# F73-M-V1_0.net
KiCad netlist of a schematic drawn in Altium Designer
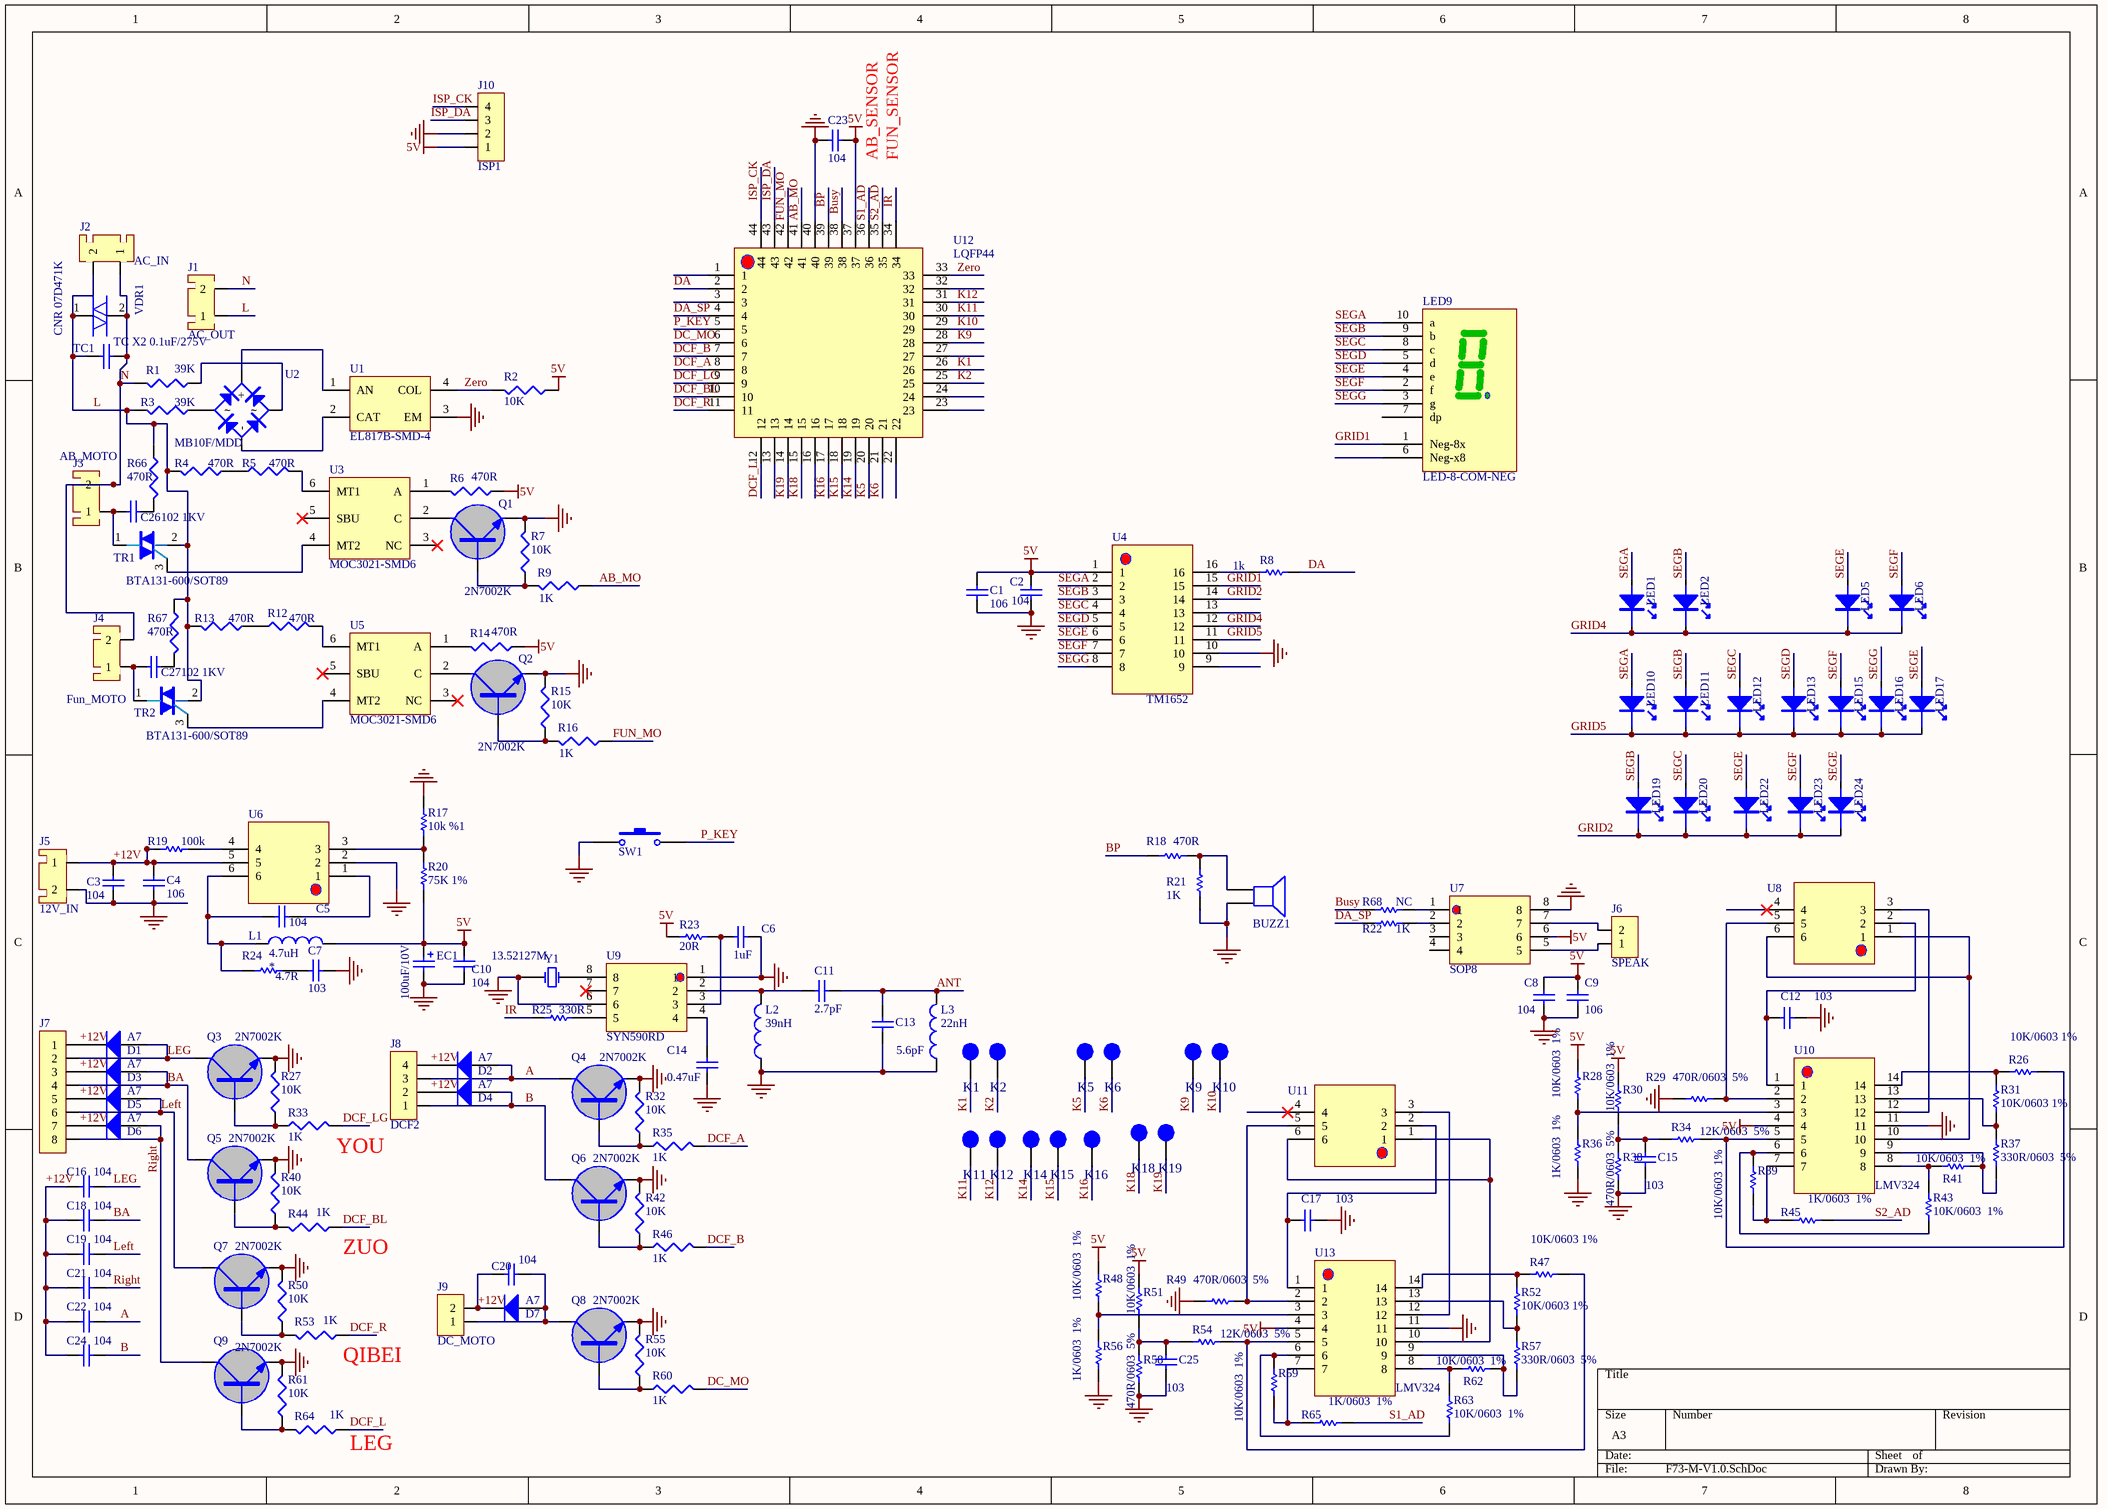
[diagram p0: F73-M-V1.0.SchDoc]

(export (version "E")
  (design (tool "Eeschema 10.0.6"))
  (components
    (comp (ref "BUZZ1")
      (value "Speaker")
      (footprint "BUZ-1407-7.5")
      (description "Loudspeaker")
      (fields (field (name "MANUFACTURER") "Generic Components"))
      (libsource (lib "Miscellaneous Devices") (part "Speaker"))
    )
    (comp (ref "C1")
      (value "106")
      (footprint "0805C")
      (description "Capacitor")
      (fields
        (field (name "MANUFACTURER") "Generic Components")
        (field (name "PUBLISHER") "Altium Hobart Technology Centre")
      )
      (libsource (lib "Miscellaneous Devices") (part "Cap"))
    )
    (comp (ref "C2")
      (value "104")
      (footprint "0603C")
      (description "Capacitor")
      (fields
        (field (name "MANUFACTURER") "Generic Components")
        (field (name "PUBLISHER") "Altium Hobart Technology Centre")
      )
      (libsource (lib "Miscellaneous Devices") (part "Cap"))
    )
    (comp (ref "C3")
      (value "104")
      (footprint "0603C")
      (description "Capacitor")
      (fields (field (name "PUBLISHER") "Altium Limited"))
      (libsource (lib "Phil") (part "Cap"))
    )
    (comp (ref "C4")
      (value "106")
      (footprint "0805C")
      (description "Capacitor")
      (fields
        (field (name "MANUFACTURER") "Generic Components")
        (field (name "PUBLISHER") "Altium Hobart Technology Centre")
      )
      (libsource (lib "Miscellaneous Devices") (part "Cap"))
    )
    (comp (ref "C5")
      (value "104")
      (footprint "0603C")
      (description "Capacitor")
      (fields
        (field (name "MANUFACTURER") "Generic Components")
        (field (name "PUBLISHER") "Altium Hobart Technology Centre")
      )
      (libsource (lib "Miscellaneous Devices") (part "Cap"))
    )
    (comp (ref "C6")
      (value "1uF")
      (footprint "0603C")
      (description "Capacitor")
      (fields (field (name "PUBLISHER") "Altium Limited"))
      (libsource (lib "Phil") (part "Cap"))
    )
    (comp (ref "C7")
      (value "103")
      (footprint "0603C")
      (description "Capacitor")
      (fields (field (name "PUBLISHER") "Altium Limited"))
      (libsource (lib "Phil") (part "Cap"))
    )
    (comp (ref "C8")
      (value "104")
      (footprint "0603C")
      (description "Capacitor")
      (fields
        (field (name "MANUFACTURER") "Generic Components")
        (field (name "PUBLISHER") "Altium Hobart Technology Centre")
      )
      (libsource (lib "Miscellaneous Devices") (part "Cap"))
    )
    (comp (ref "C9")
      (value "106")
      (footprint "0805C")
      (description "Capacitor")
      (fields
        (field (name "MANUFACTURER") "Generic Components")
        (field (name "PUBLISHER") "Altium Hobart Technology Centre")
      )
      (libsource (lib "Miscellaneous Devices") (part "Cap"))
    )
    (comp (ref "C10")
      (value "104")
      (footprint "0603C")
      (description "Capacitor")
      (fields
        (field (name "MANUFACTURER") "Generic Components")
        (field (name "PUBLISHER") "Altium Hobart Technology Centre")
      )
      (libsource (lib "Miscellaneous Devices") (part "Cap"))
    )
    (comp (ref "C11")
      (value "2.7pF")
      (footprint "0603C")
      (description "Capacitor")
      (fields (field (name "PUBLISHER") "Altium Limited"))
      (libsource (lib "Phil") (part "Cap"))
    )
    (comp (ref "C12")
      (value "103")
      (footprint "0603C")
      (description "Capacitor")
      (fields (field (name "PUBLISHER") "Altium Limited"))
      (libsource (lib "Phil") (part "Cap"))
    )
    (comp (ref "C13")
      (value "5.6pF")
      (footprint "0603C")
      (description "Capacitor")
      (fields (field (name "PUBLISHER") "Altium Limited"))
      (libsource (lib "Phil") (part "Cap"))
    )
    (comp (ref "C14")
      (value "0.47uF")
      (footprint "0603C")
      (description "Capacitor")
      (fields (field (name "PUBLISHER") "Altium Limited"))
      (libsource (lib "Phil") (part "Cap"))
    )
    (comp (ref "C15")
      (value "103")
      (footprint "0603C")
      (description "Capacitor")
      (fields (field (name "PUBLISHER") "Altium Limited"))
      (libsource (lib "Phil") (part "Cap"))
    )
    (comp (ref "C16")
      (value "104")
      (footprint "0603C")
      (description "Capacitor")
      (fields (field (name "PUBLISHER") "Altium Limited"))
      (libsource (lib "Phil") (part "Cap"))
    )
    (comp (ref "C17")
      (value "103")
      (footprint "0603C")
      (description "Capacitor")
      (fields (field (name "PUBLISHER") "Altium Limited"))
      (libsource (lib "Phil") (part "Cap"))
    )
    (comp (ref "C18")
      (value "104")
      (footprint "0603C")
      (description "Capacitor")
      (fields (field (name "PUBLISHER") "Altium Limited"))
      (libsource (lib "Phil") (part "Cap"))
    )
    (comp (ref "C19")
      (value "104")
      (footprint "0603C")
      (description "Capacitor")
      (fields (field (name "PUBLISHER") "Altium Limited"))
      (libsource (lib "Phil") (part "Cap"))
    )
    (comp (ref "C20")
      (value "104")
      (footprint "0603C")
      (description "Capacitor")
      (fields
        (field (name "MANUFACTURER") "Generic Components")
        (field (name "PUBLISHER") "Altium Hobart Technology Centre")
      )
      (libsource (lib "Miscellaneous Devices") (part "Cap"))
    )
    (comp (ref "C21")
      (value "104")
      (footprint "0603C")
      (description "Capacitor")
      (fields (field (name "PUBLISHER") "Altium Limited"))
      (libsource (lib "Phil") (part "Cap"))
    )
    (comp (ref "C22")
      (value "104")
      (footprint "0603C")
      (description "Capacitor")
      (fields (field (name "PUBLISHER") "Altium Limited"))
      (libsource (lib "Phil") (part "Cap"))
    )
    (comp (ref "C23")
      (value "104")
      (footprint "0603C")
      (description "Capacitor")
      (fields (field (name "PUBLISHER") "Altium Limited"))
      (libsource (lib "HF-FOUR-M-1.0") (part "Cap"))
    )
    (comp (ref "C24")
      (value "104")
      (footprint "0603C")
      (description "Capacitor")
      (fields (field (name "PUBLISHER") "Altium Limited"))
      (libsource (lib "Phil") (part "Cap"))
    )
    (comp (ref "C25")
      (value "103")
      (footprint "0603C")
      (description "Capacitor")
      (fields (field (name "PUBLISHER") "Altium Limited"))
      (libsource (lib "Phil") (part "Cap"))
    )
    (comp (ref "C26")
      (value "102 1KV")
      (footprint "1206C")
      (description "Capacitor")
      (fields
        (field (name "MANUFACTURER") "Generic Components")
        (field (name "PUBLISHER") "Altium Hobart Technology Centre")
      )
      (libsource (lib "Miscellaneous Devices") (part "Cap"))
    )
    (comp (ref "C27")
      (value "102 1KV")
      (footprint "1206C")
      (description "Capacitor")
      (fields
        (field (name "MANUFACTURER") "Generic Components")
        (field (name "PUBLISHER") "Altium Hobart Technology Centre")
      )
      (libsource (lib "Miscellaneous Devices") (part "Cap"))
    )
    (comp (ref "D1")
      (value "A7")
      (footprint "SOD-123FL_L2.8-W1.8-LS3.7")
      (description "1 Amp General Purpose Rectifier")
      (fields (field (name "PUBLISHER") "Altium Limited"))
      (libsource (lib "Phil") (part "Diode 1N4007"))
    )
    (comp (ref "D2")
      (value "A7")
      (footprint "SOD-123FL_L2.8-W1.8-LS3.7")
      (description "1 Amp General Purpose Rectifier")
      (fields (field (name "PUBLISHER") "Altium Limited"))
      (libsource (lib "Phil") (part "Diode 1N4007"))
    )
    (comp (ref "D3")
      (value "A7")
      (footprint "SOD-123FL_L2.8-W1.8-LS3.7")
      (description "1 Amp General Purpose Rectifier")
      (fields (field (name "PUBLISHER") "Altium Limited"))
      (libsource (lib "Phil") (part "Diode 1N4007"))
    )
    (comp (ref "D4")
      (value "A7")
      (footprint "SOD-123FL_L2.8-W1.8-LS3.7")
      (description "1 Amp General Purpose Rectifier")
      (fields (field (name "PUBLISHER") "Altium Limited"))
      (libsource (lib "Phil") (part "Diode 1N4007"))
    )
    (comp (ref "D5")
      (value "A7")
      (footprint "SOD-123FL_L2.8-W1.8-LS3.7")
      (description "1 Amp General Purpose Rectifier")
      (fields (field (name "PUBLISHER") "Altium Limited"))
      (libsource (lib "Phil") (part "Diode 1N4007"))
    )
    (comp (ref "D6")
      (value "A7")
      (footprint "SOD-123FL_L2.8-W1.8-LS3.7")
      (description "1 Amp General Purpose Rectifier")
      (fields (field (name "PUBLISHER") "Altium Limited"))
      (libsource (lib "Phil") (part "Diode 1N4007"))
    )
    (comp (ref "D7")
      (value "A7")
      (footprint "SOD-123FL_L2.8-W1.8-LS3.7")
      (description "1 Amp General Purpose Rectifier")
      (fields (field (name "PUBLISHER") "Altium Limited"))
      (libsource (lib "Phil") (part "Diode 1N4007"))
    )
    (comp (ref "EC1")
      (value "100uF/10V")
      (footprint "CAP SMD 6.3*5.5mm")
      (description "Polarized Capacitor (Radial)")
      (fields
        (field (name "MANUFACTURER") "Generic Components")
        (field (name "PUBLISHER") "Altium Hobart Technology Centre")
      )
      (libsource (lib "Miscellaneous Devices") (part "Cap Pol1"))
    )
    (comp (ref "J1")
      (value "AC_OUT")
      (footprint "K-VH3.96-3P")
      (libsource (lib "SCH Connector(2019-4-13)") (part "PITCH3.96-5.0-2A"))
    )
    (comp (ref "J2")
      (value "AC_IN")
      (footprint "K-VH3.96-3P")
      (libsource (lib "") (part "PITCH3.96-5.0-2A_1"))
    )
    (comp (ref "J3")
      (value "AB_MOTO")
      (footprint "K-VH3.96-3P")
      (libsource (lib "SCH Connector(2019-4-13)") (part "PITCH3.96-5.0-2A"))
    )
    (comp (ref "J4")
      (value "Fun_MOTO")
      (footprint "K-VH3.96-3P")
      (libsource (lib "SCH Connector(2019-4-13)") (part "PITCH3.96-5.0-2A"))
    )
    (comp (ref "J5")
      (value "12V_IN")
      (footprint "CON2-SMD-XHB 2*2.5MM")
      (libsource (lib "SCH Connector(2019-4-13)") (part "PITCH2.5-2A"))
    )
    (comp (ref "J6") (value "SPEAK") (footprint "CON2-SMD_PH2.0-1X2PW") (libsource (lib "") (part "CON2_1")))
    (comp (ref "J7")
      (value "~")
      (footprint "CON8-SMD-XHB 8*2.5MM")
      (libsource (lib "HF-FOUR-M-1.0") (part "CON8"))
    )
    (comp (ref "J8")
      (value "DCF2")
      (footprint "CON4-SMD_4P-P2.54_XH2.54-4AB")
      (libsource (lib "Phil") (part "CON4"))
    )
    (comp (ref "J9")
      (value "DC_MOTO")
      (footprint "CON2-SMD-XHB 2*2.5MM")
      (libsource (lib "Phil") (part "CON2"))
    )
    (comp (ref "J10") (value "ISP1") (footprint "CON4 -2.54-H") (libsource (lib "") (part "CON4_1")))
    (comp (ref "K1")
      (value "Φ15 H8mm弹簧")
      (footprint "TK_HF-13*13*8")
      (libsource (lib "HF-FOUR-M-1.0") (part "TOUCH-PAD"))
    )
    (comp (ref "K2")
      (value "Φ15 H8mm弹簧")
      (footprint "TK_HF-13*13*8")
      (libsource (lib "HF-FOUR-M-1.0") (part "TOUCH-PAD"))
    )
    (comp (ref "K5")
      (value "Φ15 H8mm弹簧")
      (footprint "TK_HF-13*13*8")
      (libsource (lib "HF-FOUR-M-1.0") (part "TOUCH-PAD"))
    )
    (comp (ref "K6")
      (value "Φ15 H8mm弹簧")
      (footprint "TK_HF-13*13*8")
      (libsource (lib "HF-FOUR-M-1.0") (part "TOUCH-PAD"))
    )
    (comp (ref "K9")
      (value "Φ15 H8mm弹簧")
      (footprint "TK_HF-13*13*8")
      (libsource (lib "HF-FOUR-M-1.0") (part "TOUCH-PAD"))
    )
    (comp (ref "K10")
      (value "Φ15 H8mm弹簧")
      (footprint "TK_HF-13*13*8")
      (libsource (lib "HF-FOUR-M-1.0") (part "TOUCH-PAD"))
    )
    (comp (ref "K11")
      (value "Φ15 H8mm弹簧")
      (footprint "TK_HF-13*13*8")
      (libsource (lib "HF-FOUR-M-1.0") (part "TOUCH-PAD"))
    )
    (comp (ref "K12")
      (value "Φ15 H8mm弹簧")
      (footprint "TK_HF-13*13*8")
      (libsource (lib "HF-FOUR-M-1.0") (part "TOUCH-PAD"))
    )
    (comp (ref "K14")
      (value "Φ15 H8mm弹簧")
      (footprint "TK_HF-13*13*8")
      (libsource (lib "HF-FOUR-M-1.0") (part "TOUCH-PAD"))
    )
    (comp (ref "K15")
      (value "Φ15 H8mm弹簧")
      (footprint "TK_HF-13*13*8")
      (libsource (lib "HF-FOUR-M-1.0") (part "TOUCH-PAD"))
    )
    (comp (ref "K16")
      (value "Φ15 H8mm弹簧")
      (footprint "TK_HF-13*13*8")
      (libsource (lib "HF-FOUR-M-1.0") (part "TOUCH-PAD"))
    )
    (comp (ref "K18")
      (value "Φ15 H8mm弹簧")
      (footprint "TK_HF-13*13*8")
      (libsource (lib "HF-FOUR-M-1.0") (part "TOUCH-PAD"))
    )
    (comp (ref "K19")
      (value "Φ15 H8mm弹簧")
      (footprint "TK_HF-13*13*8")
      (libsource (lib "HF-FOUR-M-1.0") (part "TOUCH-PAD"))
    )
    (comp (ref "L1")
      (value "4.7uH")
      (footprint "INDC5050")
      (description "Inductor")
      (fields (field (name "ALTIUM_VALUE") "*") (field (name "PUBLISHER") "Altium Limited"))
      (libsource (lib "Phil") (part "Inductor"))
    )
    (comp (ref "L2")
      (value "39nH")
      (footprint "0603R")
      (description "Inductor")
      (fields (field (name "PUBLISHER") "Altium Limited"))
      (libsource (lib "Phil") (part "Inductor"))
    )
    (comp (ref "L3")
      (value "22nH")
      (footprint "0603R")
      (description "Inductor")
      (fields (field (name "PUBLISHER") "Altium Limited"))
      (libsource (lib "Phil") (part "Inductor"))
    )
    (comp (ref "LED1") (value "LED_0603") (footprint "LED_0603") (libsource (lib "Phil") (part "LED")))
    (comp (ref "LED2") (value "LED_0603") (footprint "LED_0603") (libsource (lib "Phil") (part "LED")))
    (comp (ref "LED5") (value "LED_0603") (footprint "LED_0603") (libsource (lib "Phil") (part "LED")))
    (comp (ref "LED6") (value "LED_0603") (footprint "LED_0603") (libsource (lib "Phil") (part "LED")))
    (comp (ref "LED9")
      (value "LED-8-COM-NEG")
      (footprint "LED1B-10P(7.5*14*H8.5 P2.54*10.16)")
      (libsource (lib "F73-M-V1.0") (part "LED-8-COM-NEG"))
    )
    (comp (ref "LED10") (value "LED_0603") (footprint "LED_0603") (libsource (lib "Phil") (part "LED")))
    (comp (ref "LED11") (value "LED_0603") (footprint "LED_0603") (libsource (lib "Phil") (part "LED")))
    (comp (ref "LED12") (value "LED_0603") (footprint "LED_0603") (libsource (lib "Phil") (part "LED")))
    (comp (ref "LED13") (value "LED_0603") (footprint "LED_0603") (libsource (lib "Phil") (part "LED")))
    (comp (ref "LED15") (value "LED_0603") (footprint "LED_0603") (libsource (lib "Phil") (part "LED")))
    (comp (ref "LED16") (value "LED_0603") (footprint "LED_0603") (libsource (lib "Phil") (part "LED")))
    (comp (ref "LED17") (value "LED_0603") (footprint "LED_0603") (libsource (lib "Phil") (part "LED")))
    (comp (ref "LED19") (value "LED_0603") (footprint "LED_0603") (libsource (lib "Phil") (part "LED")))
    (comp (ref "LED20") (value "LED_0603") (footprint "LED_0603") (libsource (lib "Phil") (part "LED")))
    (comp (ref "LED22") (value "LED_0603") (footprint "LED_0603") (libsource (lib "Phil") (part "LED")))
    (comp (ref "LED23") (value "LED_0603") (footprint "LED_0603") (libsource (lib "Phil") (part "LED")))
    (comp (ref "LED24") (value "LED_0603") (footprint "LED_0603") (libsource (lib "Phil") (part "LED")))
    (comp (ref "Q1")
      (value "2N7002K")
      (footprint "SOT-23 - MOS")
      (libsource (lib "SCH-Transistor-Triac-Mosfet(2018-9-19-1)") (part "NPN-8050-BCE-25V/500mA"))
    )
    (comp (ref "Q2")
      (value "2N7002K")
      (footprint "SOT-23 - MOS")
      (libsource (lib "SCH-Transistor-Triac-Mosfet(2018-9-19-1)") (part "NPN-8050-BCE-25V/500mA"))
    )
    (comp (ref "Q3")
      (value "2N7002K")
      (footprint "SOT-23 - MOS")
      (libsource (lib "SCH-Transistor-Triac-Mosfet(2018-9-19-1)") (part "NPN-8050-BCE-25V/500mA"))
    )
    (comp (ref "Q4")
      (value "2N7002K")
      (footprint "SOT-23 - MOS")
      (libsource (lib "SCH-Transistor-Triac-Mosfet(2018-9-19-1)") (part "NPN-8050-BCE-25V/500mA"))
    )
    (comp (ref "Q5")
      (value "2N7002K")
      (footprint "SOT-23 - MOS")
      (libsource (lib "SCH-Transistor-Triac-Mosfet(2018-9-19-1)") (part "NPN-8050-BCE-25V/500mA"))
    )
    (comp (ref "Q6")
      (value "2N7002K")
      (footprint "SOT-23 - MOS")
      (libsource (lib "SCH-Transistor-Triac-Mosfet(2018-9-19-1)") (part "NPN-8050-BCE-25V/500mA"))
    )
    (comp (ref "Q7")
      (value "2N7002K")
      (footprint "SOT-23 - MOS")
      (libsource (lib "SCH-Transistor-Triac-Mosfet(2018-9-19-1)") (part "NPN-8050-BCE-25V/500mA"))
    )
    (comp (ref "Q8")
      (value "2N7002K")
      (footprint "SOT-23 - MOS")
      (libsource (lib "SCH-Transistor-Triac-Mosfet(2018-9-19-1)") (part "NPN-8050-BCE-25V/500mA"))
    )
    (comp (ref "Q9")
      (value "2N7002K")
      (footprint "SOT-23 - MOS")
      (libsource (lib "SCH-Transistor-Triac-Mosfet(2018-9-19-1)") (part "NPN-8050-BCE-25V/500mA"))
    )
    (comp (ref "R1")
      (value "39K")
      (footprint "1206R")
      (libsource (lib "SCH Resistor(2019-6-10)") (part "1Ω±1%/0805-1206"))
    )
    (comp (ref "R2")
      (value "10K")
      (footprint "0603")
      (libsource (lib "SCH Resistor(2019-6-10)") (part "1Ω±1%/0603-0805"))
    )
    (comp (ref "R3")
      (value "39K")
      (footprint "1206R")
      (libsource (lib "SCH Resistor(2019-6-10)") (part "1Ω±1%/0805-1206"))
    )
    (comp (ref "R4")
      (value "470R")
      (footprint "1206R")
      (libsource (lib "SCH Resistor(2019-6-10)") (part "1Ω±1%/0805-1206"))
    )
    (comp (ref "R5")
      (value "470R")
      (footprint "1206R")
      (libsource (lib "SCH Resistor(2019-6-10)") (part "1Ω±1%/0805-1206"))
    )
    (comp (ref "R6")
      (value "470R")
      (footprint "0603")
      (libsource (lib "SCH Resistor(2019-6-10)") (part "1Ω±1%/0603-0805"))
    )
    (comp (ref "R7")
      (value "10K")
      (footprint "0603")
      (libsource (lib "SCH Resistor(2019-6-10)") (part "1Ω±1%/0603-0805"))
    )
    (comp (ref "R8")
      (value "1k")
      (footprint "0603R")
      (description "Resistor")
      (fields (field (name "PUBLISHER") "Altium Limited"))
      (libsource (lib "Phil") (part "Res1"))
    )
    (comp (ref "R9")
      (value "1K")
      (footprint "0603")
      (libsource (lib "SCH Resistor(2019-6-10)") (part "1Ω±1%/0603-0805"))
    )
    (comp (ref "R12")
      (value "470R")
      (footprint "1206R")
      (libsource (lib "SCH Resistor(2019-6-10)") (part "1Ω±1%/0805-1206"))
    )
    (comp (ref "R13")
      (value "470R")
      (footprint "1206R")
      (libsource (lib "SCH Resistor(2019-6-10)") (part "1Ω±1%/0805-1206"))
    )
    (comp (ref "R14")
      (value "470R")
      (footprint "0603")
      (libsource (lib "SCH Resistor(2019-6-10)") (part "1Ω±1%/0603-0805"))
    )
    (comp (ref "R15")
      (value "10K")
      (footprint "0603")
      (libsource (lib "SCH Resistor(2019-6-10)") (part "1Ω±1%/0603-0805"))
    )
    (comp (ref "R16")
      (value "1K")
      (footprint "0603")
      (libsource (lib "SCH Resistor(2019-6-10)") (part "1Ω±1%/0603-0805"))
    )
    (comp (ref "R17")
      (value "10k %1")
      (footprint "0603R")
      (description "Resistor")
      (fields (field (name "PUBLISHER") "Altium Limited"))
      (libsource (lib "Phil") (part "Res1"))
    )
    (comp (ref "R18")
      (value "470R")
      (footprint "0603R")
      (description "Resistor")
      (fields (field (name "PUBLISHER") "Altium Limited"))
      (libsource (lib "Phil") (part "Res1"))
    )
    (comp (ref "R19")
      (value "100k")
      (footprint "0603R")
      (description "Resistor")
      (fields (field (name "PUBLISHER") "Altium Limited"))
      (libsource (lib "Phil") (part "Res1"))
    )
    (comp (ref "R20")
      (value "75K 1%")
      (footprint "0603R")
      (description "Resistor")
      (fields (field (name "PUBLISHER") "Altium Limited"))
      (libsource (lib "Phil") (part "Res1"))
    )
    (comp (ref "R21")
      (value "1K")
      (footprint "0603R")
      (description "Resistor")
      (fields (field (name "PUBLISHER") "Altium Limited"))
      (libsource (lib "Phil") (part "Res1"))
    )
    (comp (ref "R22")
      (value "1K")
      (footprint "0603R")
      (description "Resistor")
      (fields (field (name "PUBLISHER") "Altium Limited"))
      (libsource (lib "Phil") (part "Res1"))
    )
    (comp (ref "R23")
      (value "20R")
      (footprint "0603R")
      (description "Resistor")
      (fields (field (name "PUBLISHER") "Altium Limited"))
      (libsource (lib "Phil") (part "Res1"))
    )
    (comp (ref "R24")
      (value "4.7R")
      (footprint "0603R")
      (description "Resistor")
      (fields (field (name "PUBLISHER") "Altium Limited"))
      (libsource (lib "Phil") (part "Res1"))
    )
    (comp (ref "R25")
      (value "330R")
      (footprint "0603R")
      (description "Resistor")
      (fields (field (name "PUBLISHER") "Altium Limited"))
      (libsource (lib "Phil") (part "Res1"))
    )
    (comp (ref "R26")
      (value "10K/0603 1%")
      (footprint "0603R")
      (description "Resistor")
      (fields (field (name "PUBLISHER") "Altium Limited"))
      (libsource (lib "Phil") (part "Res1"))
    )
    (comp (ref "R27")
      (value "10K")
      (footprint "0603")
      (libsource (lib "SCH Resistor(2019-6-10)") (part "1Ω±1%/0603-0805"))
    )
    (comp (ref "R28")
      (value "10K/0603  1%")
      (footprint "0603R")
      (description "Resistor")
      (fields (field (name "PUBLISHER") "Altium Limited"))
      (libsource (lib "Phil") (part "Res1"))
    )
    (comp (ref "R29")
      (value "470R/0603  5%")
      (footprint "0603R")
      (description "Resistor")
      (fields (field (name "PUBLISHER") "Altium Limited"))
      (libsource (lib "Phil") (part "Res1"))
    )
    (comp (ref "R30")
      (value "10K/0603  1%")
      (footprint "0603R")
      (description "Resistor")
      (fields (field (name "PUBLISHER") "Altium Limited"))
      (libsource (lib "Phil") (part "Res1"))
    )
    (comp (ref "R31")
      (value "10K/0603 1%")
      (footprint "0603R")
      (description "Resistor")
      (fields (field (name "PUBLISHER") "Altium Limited"))
      (libsource (lib "Phil") (part "Res1"))
    )
    (comp (ref "R32")
      (value "10K")
      (footprint "0603")
      (libsource (lib "SCH Resistor(2019-6-10)") (part "1Ω±1%/0603-0805"))
    )
    (comp (ref "R33")
      (value "1K")
      (footprint "0603")
      (libsource (lib "SCH Resistor(2019-6-10)") (part "1Ω±1%/0603-0805"))
    )
    (comp (ref "R34")
      (value "12K/0603  5%")
      (footprint "0603R")
      (description "Resistor")
      (fields (field (name "PUBLISHER") "Altium Limited"))
      (libsource (lib "Phil") (part "Res1"))
    )
    (comp (ref "R35")
      (value "1K")
      (footprint "0603")
      (libsource (lib "SCH Resistor(2019-6-10)") (part "1Ω±1%/0603-0805"))
    )
    (comp (ref "R36")
      (value "1K/0603  1%")
      (footprint "0603R")
      (description "Resistor")
      (fields (field (name "PUBLISHER") "Altium Limited"))
      (libsource (lib "Phil") (part "Res1"))
    )
    (comp (ref "R37")
      (value "330R/0603  5%")
      (footprint "0603R")
      (description "Resistor")
      (fields (field (name "PUBLISHER") "Altium Limited"))
      (libsource (lib "Phil") (part "Res1"))
    )
    (comp (ref "R38")
      (value "470R/0603  5%")
      (footprint "0603R")
      (description "Resistor")
      (fields (field (name "PUBLISHER") "Altium Limited"))
      (libsource (lib "Phil") (part "Res1"))
    )
    (comp (ref "R39")
      (value "10K/0603  1%")
      (footprint "0603R")
      (description "Resistor")
      (fields (field (name "PUBLISHER") "Altium Limited"))
      (libsource (lib "Phil") (part "Res1"))
    )
    (comp (ref "R40")
      (value "10K")
      (footprint "0603")
      (libsource (lib "SCH Resistor(2019-6-10)") (part "1Ω±1%/0603-0805"))
    )
    (comp (ref "R41")
      (value "10K/0603  1%")
      (footprint "0603R")
      (description "Resistor")
      (fields (field (name "PUBLISHER") "Altium Limited"))
      (libsource (lib "Phil") (part "Res1"))
    )
    (comp (ref "R42")
      (value "10K")
      (footprint "0603")
      (libsource (lib "SCH Resistor(2019-6-10)") (part "1Ω±1%/0603-0805"))
    )
    (comp (ref "R43")
      (value "10K/0603  1%")
      (footprint "0603R")
      (description "Resistor")
      (fields (field (name "PUBLISHER") "Altium Limited"))
      (libsource (lib "Phil") (part "Res1"))
    )
    (comp (ref "R44")
      (value "1K")
      (footprint "0603")
      (libsource (lib "SCH Resistor(2019-6-10)") (part "1Ω±1%/0603-0805"))
    )
    (comp (ref "R45")
      (value "1K/0603  1%")
      (footprint "0603R")
      (description "Resistor")
      (fields (field (name "PUBLISHER") "Altium Limited"))
      (libsource (lib "Phil") (part "Res1"))
    )
    (comp (ref "R46")
      (value "1K")
      (footprint "0603")
      (libsource (lib "SCH Resistor(2019-6-10)") (part "1Ω±1%/0603-0805"))
    )
    (comp (ref "R47")
      (value "10K/0603 1%")
      (footprint "0603R")
      (description "Resistor")
      (fields (field (name "PUBLISHER") "Altium Limited"))
      (libsource (lib "Phil") (part "Res1"))
    )
    (comp (ref "R48")
      (value "10K/0603  1%")
      (footprint "0603R")
      (description "Resistor")
      (fields (field (name "PUBLISHER") "Altium Limited"))
      (libsource (lib "Phil") (part "Res1"))
    )
    (comp (ref "R49")
      (value "470R/0603  5%")
      (footprint "0603R")
      (description "Resistor")
      (fields (field (name "PUBLISHER") "Altium Limited"))
      (libsource (lib "Phil") (part "Res1"))
    )
    (comp (ref "R50")
      (value "10K")
      (footprint "0603")
      (libsource (lib "SCH Resistor(2019-6-10)") (part "1Ω±1%/0603-0805"))
    )
    (comp (ref "R51")
      (value "10K/0603  1%")
      (footprint "0603R")
      (description "Resistor")
      (fields (field (name "PUBLISHER") "Altium Limited"))
      (libsource (lib "Phil") (part "Res1"))
    )
    (comp (ref "R52")
      (value "10K/0603 1%")
      (footprint "0603R")
      (description "Resistor")
      (fields (field (name "PUBLISHER") "Altium Limited"))
      (libsource (lib "Phil") (part "Res1"))
    )
    (comp (ref "R53")
      (value "1K")
      (footprint "0603")
      (libsource (lib "SCH Resistor(2019-6-10)") (part "1Ω±1%/0603-0805"))
    )
    (comp (ref "R54")
      (value "12K/0603  5%")
      (footprint "0603R")
      (description "Resistor")
      (fields (field (name "PUBLISHER") "Altium Limited"))
      (libsource (lib "Phil") (part "Res1"))
    )
    (comp (ref "R55")
      (value "10K")
      (footprint "0603")
      (libsource (lib "SCH Resistor(2019-6-10)") (part "1Ω±1%/0603-0805"))
    )
    (comp (ref "R56")
      (value "1K/0603  1%")
      (footprint "0603R")
      (description "Resistor")
      (fields (field (name "PUBLISHER") "Altium Limited"))
      (libsource (lib "Phil") (part "Res1"))
    )
    (comp (ref "R57")
      (value "330R/0603  5%")
      (footprint "0603R")
      (description "Resistor")
      (fields (field (name "PUBLISHER") "Altium Limited"))
      (libsource (lib "Phil") (part "Res1"))
    )
    (comp (ref "R58")
      (value "470R/0603  5%")
      (footprint "0603R")
      (description "Resistor")
      (fields (field (name "PUBLISHER") "Altium Limited"))
      (libsource (lib "Phil") (part "Res1"))
    )
    (comp (ref "R59")
      (value "10K/0603  1%")
      (footprint "0603R")
      (description "Resistor")
      (fields (field (name "PUBLISHER") "Altium Limited"))
      (libsource (lib "Phil") (part "Res1"))
    )
    (comp (ref "R60")
      (value "1K")
      (footprint "0603")
      (libsource (lib "SCH Resistor(2019-6-10)") (part "1Ω±1%/0603-0805"))
    )
    (comp (ref "R61")
      (value "10K")
      (footprint "0603")
      (libsource (lib "SCH Resistor(2019-6-10)") (part "1Ω±1%/0603-0805"))
    )
    (comp (ref "R62")
      (value "10K/0603  1%")
      (footprint "0603R")
      (description "Resistor")
      (fields (field (name "PUBLISHER") "Altium Limited"))
      (libsource (lib "Phil") (part "Res1"))
    )
    (comp (ref "R63")
      (value "10K/0603  1%")
      (footprint "0603R")
      (description "Resistor")
      (fields (field (name "PUBLISHER") "Altium Limited"))
      (libsource (lib "Phil") (part "Res1"))
    )
    (comp (ref "R64")
      (value "1K")
      (footprint "0603")
      (libsource (lib "SCH Resistor(2019-6-10)") (part "1Ω±1%/0603-0805"))
    )
    (comp (ref "R65")
      (value "1K/0603  1%")
      (footprint "0603R")
      (description "Resistor")
      (fields (field (name "PUBLISHER") "Altium Limited"))
      (libsource (lib "Phil") (part "Res1"))
    )
    (comp (ref "R66")
      (value "470R")
      (footprint "1206R")
      (libsource (lib "SCH Resistor(2019-6-10)") (part "1Ω±1%/0805-1206"))
    )
    (comp (ref "R67")
      (value "470R")
      (footprint "1206R")
      (libsource (lib "SCH Resistor(2019-6-10)") (part "1Ω±1%/0805-1206"))
    )
    (comp (ref "R68")
      (value "NC")
      (footprint "0603R")
      (description "Resistor")
      (fields (field (name "PUBLISHER") "Altium Limited"))
      (libsource (lib "Phil") (part "Res1"))
    )
    (comp (ref "SW1")
      (value "SW-PB")
      (footprint "BUTTON-SMD-6*6*10")
      (description "Switch")
      (fields (field (name "PUBLISHER") "Altium Limited"))
      (libsource (lib "Phil") (part "SW-PB"))
    )
    (comp (ref "TC1")
      (value "TC X2 0.1uF/275V")
      (footprint "CAP-TH_L13.0-W6.0-P10.00-D0.6")
      (libsource (lib "TEL SCH") (part "CAP1"))
    )
    (comp (ref "TR1")
      (value "BTA131-600/SOT89")
      (footprint "SOT-89 BT131-600")
      (libsource (lib "TEL SCH") (part "Triac"))
    )
    (comp (ref "TR2")
      (value "BTA131-600/SOT89")
      (footprint "SOT-89 BT131-600")
      (libsource (lib "TEL SCH") (part "Triac"))
    )
    (comp (ref "U1")
      (value "EL817B-SMD-4")
      (footprint "PC817-smd")
      (libsource (lib "SCH IC-Power(2019-2-14)") (part "EL817-DIP-4"))
    )
    (comp (ref "U2")
      (value "MB10F/MDD")
      (footprint "DB-MB10F")
      (description "Diode Bridge")
      (libsource (lib "SCH Diode-Bridge-Zener(2018-10-15)") (part "BD-ABS10/MB10S"))
    )
    (comp (ref "U3")
      (value "MOC3021-SMD6")
      (footprint "SMD6")
      (libsource (lib "SCH IC-Power(2019-2-14)") (part "MOC3021-DIP-6"))
    )
    (comp (ref "U4") (value "TM1652") (footprint "SOP16(150MIL)") (libsource (lib "Phil") (part "SOP16")))
    (comp (ref "U5")
      (value "MOC3021-SMD6")
      (footprint "SMD6")
      (libsource (lib "SCH IC-Power(2019-2-14)") (part "MOC3021-DIP-6"))
    )
    (comp (ref "U6") (value "HT7712") (footprint "SOT23-6_M") (libsource (lib "Phil") (part "SOP6")))
    (comp (ref "U7") (value "SOP8") (footprint "SOP8-SS") (libsource (lib "") (part "SOP8_1")))
    (comp (ref "U8") (value "SOP6") (footprint "PSG010R/S") (libsource (lib "Phil") (part "SOP6")))
    (comp (ref "U9") (value "SYN590RD") (footprint "SOP8(5.1*6.2mm)") (libsource (lib "Phil") (part "SOP8")))
    (comp (ref "U10") (value "LMV324") (footprint "SOP14(150mil)") (libsource (lib "Phil") (part "SOP14")))
    (comp (ref "U11") (value "SOP6") (footprint "PSG010R/S") (libsource (lib "Phil") (part "SOP6")))
    (comp (ref "U12") (value "LQFP44") (footprint "LQFP44") (libsource (lib "Phil") (part "LQFP44")))
    (comp (ref "U13") (value "LMV324") (footprint "SOP14(150mil)") (libsource (lib "Phil") (part "SOP14")))
    (comp (ref "VDR1")
      (value "CNR 07D471K")
      (footprint "RES-TH_L9.0-W5.0-P5-D0.7-S3.00")
      (libsource (lib "LZB_SCH") (part "VAR"))
    )
    (comp (ref "Y1")
      (value "13.52127M")
      (footprint "HC-49S_L11.4-W4.8")
      (description "Crystal Oscillator")
      (fields (field (name "PUBLISHER") "Altium Limited"))
      (libsource (lib "Phil") (part "XTAL"))
    )
  )
  (nets
    (net (code "1") (name "/+12V") (class "Default")
      (node (ref "C16") (pin "1") (pinfunction "1_1") (pintype "passive"))
      (node (ref "C18") (pin "1") (pinfunction "1_1") (pintype "passive"))
      (node (ref "C19") (pin "1") (pinfunction "1_1") (pintype "passive"))
      (node (ref "C20") (pin "1") (pinfunction "1_1") (pintype "passive"))
      (node (ref "C21") (pin "1") (pinfunction "1_1") (pintype "passive"))
      (node (ref "C22") (pin "1") (pinfunction "1_1") (pintype "passive"))
      (node (ref "C24") (pin "1") (pinfunction "1_1") (pintype "passive"))
      (node (ref "C3") (pin "1") (pinfunction "1_1") (pintype "passive"))
      (node (ref "C4") (pin "1") (pinfunction "1_1") (pintype "passive"))
      (node (ref "D1") (pin "2") (pinfunction "K_2") (pintype "passive"))
      (node (ref "D2") (pin "2") (pinfunction "K_2") (pintype "passive"))
      (node (ref "D3") (pin "2") (pinfunction "K_2") (pintype "passive"))
      (node (ref "D4") (pin "2") (pinfunction "K_2") (pintype "passive"))
      (node (ref "D5") (pin "2") (pinfunction "K_2") (pintype "passive"))
      (node (ref "D6") (pin "2") (pinfunction "K_2") (pintype "passive"))
      (node (ref "D7") (pin "2") (pinfunction "K_2") (pintype "passive"))
      (node (ref "J5") (pin "1") (pinfunction "1_1") (pintype "passive"))
      (node (ref "J7") (pin "1") (pinfunction "1_1") (pintype "passive"))
      (node (ref "J7") (pin "3") (pinfunction "3_3") (pintype "passive"))
      (node (ref "J7") (pin "5") (pinfunction "5_5") (pintype "passive"))
      (node (ref "J7") (pin "7") (pinfunction "7_7") (pintype "passive"))
      (node (ref "J8") (pin "2") (pinfunction "2_2") (pintype "passive"))
      (node (ref "J8") (pin "4") (pinfunction "4_4") (pintype "passive"))
      (node (ref "J9") (pin "2") (pinfunction "2_2") (pintype "passive"))
      (node (ref "R19") (pin "1") (pinfunction "1_1") (pintype "passive"))
      (node (ref "U6") (pin "5") (pinfunction "5_5") (pintype "passive"))
    )
    (net (code "2") (name "/A") (class "Default")
      (node (ref "C22") (pin "2") (pinfunction "2_2") (pintype "passive"))
      (node (ref "D2") (pin "1") (pinfunction "A_1") (pintype "passive"))
      (node (ref "J8") (pin "3") (pinfunction "3_3") (pintype "passive"))
      (node (ref "Q4") (pin "C") (pinfunction "C_C") (pintype "passive"))
    )
    (net (code "3") (name "/AB_MO") (class "Default")
      (node (ref "R9") (pin "1") (pintype "passive"))
      (node (ref "U12") (pin "41") (pinfunction "41_41") (pintype "passive"))
    )
    (net (code "4") (name "/ANT") (class "Default")
      (node (ref "C11") (pin "1") (pinfunction "1_1") (pintype "passive"))
      (node (ref "C13") (pin "2") (pinfunction "2_2") (pintype "passive"))
      (node (ref "L3") (pin "2") (pinfunction "2_2") (pintype "passive"))
    )
    (net (code "5") (name "/B") (class "Default")
      (node (ref "C24") (pin "2") (pinfunction "2_2") (pintype "passive"))
      (node (ref "D4") (pin "1") (pinfunction "A_1") (pintype "passive"))
      (node (ref "J8") (pin "1") (pinfunction "1_1") (pintype "passive"))
      (node (ref "Q6") (pin "C") (pinfunction "C_C") (pintype "passive"))
    )
    (net (code "6") (name "/BA") (class "Default")
      (node (ref "C18") (pin "2") (pinfunction "2_2") (pintype "passive"))
      (node (ref "D3") (pin "1") (pinfunction "A_1") (pintype "passive"))
      (node (ref "J7") (pin "4") (pinfunction "4_4") (pintype "passive"))
      (node (ref "Q5") (pin "C") (pinfunction "C_C") (pintype "passive"))
    )
    (net (code "7") (name "/BP") (class "Default")
      (node (ref "R18") (pin "2") (pinfunction "2_2") (pintype "passive"))
      (node (ref "U12") (pin "39") (pinfunction "39_39") (pintype "passive"))
    )
    (net (code "8") (name "/Busy") (class "Default")
      (node (ref "R68") (pin "1") (pinfunction "1_1") (pintype "passive"))
      (node (ref "U12") (pin "38") (pinfunction "38_38") (pintype "passive"))
    )
    (net (code "9") (name "/DA") (class "Default")
      (node (ref "R8") (pin "1") (pinfunction "1_1") (pintype "passive"))
      (node (ref "U12") (pin "2") (pinfunction "2_2") (pintype "passive"))
    )
    (net (code "10") (name "/DA_SP") (class "Default")
      (node (ref "R22") (pin "1") (pinfunction "1_1") (pintype "passive"))
      (node (ref "U12") (pin "4") (pinfunction "4_4") (pintype "passive"))
    )
    (net (code "11") (name "/DCF_A") (class "Default")
      (node (ref "R35") (pin "2") (pintype "passive"))
      (node (ref "U12") (pin "8") (pinfunction "8_8") (pintype "passive"))
    )
    (net (code "12") (name "/DCF_B") (class "Default")
      (node (ref "R46") (pin "2") (pintype "passive"))
      (node (ref "U12") (pin "7") (pinfunction "7_7") (pintype "passive"))
    )
    (net (code "13") (name "/DCF_BL") (class "Default")
      (node (ref "R44") (pin "1") (pintype "passive"))
      (node (ref "U12") (pin "10") (pinfunction "10_10") (pintype "passive"))
    )
    (net (code "14") (name "/DCF_L") (class "Default")
      (node (ref "R64") (pin "1") (pintype "passive"))
      (node (ref "U12") (pin "12") (pinfunction "12_12") (pintype "passive"))
    )
    (net (code "15") (name "/DCF_LG") (class "Default")
      (node (ref "R33") (pin "2") (pintype "passive"))
      (node (ref "U12") (pin "9") (pinfunction "9_9") (pintype "passive"))
    )
    (net (code "16") (name "/DCF_R") (class "Default")
      (node (ref "R53") (pin "1") (pintype "passive"))
      (node (ref "U12") (pin "11") (pinfunction "11_11") (pintype "passive"))
    )
    (net (code "17") (name "/DC_MO") (class "Default")
      (node (ref "R60") (pin "2") (pintype "passive"))
      (node (ref "U12") (pin "6") (pinfunction "6_6") (pintype "passive"))
    )
    (net (code "18") (name "/FUN_MO") (class "Default")
      (node (ref "R16") (pin "1") (pintype "passive"))
      (node (ref "U12") (pin "42") (pinfunction "42_42") (pintype "passive"))
    )
    (net (code "19") (name "/GRID1") (class "Default")
      (node (ref "LED9") (pin "1") (pinfunction "Neg-8x_1") (pintype "passive"))
      (node (ref "U4") (pin "15") (pinfunction "15_15") (pintype "passive"))
    )
    (net (code "20") (name "/GRID2") (class "Default")
      (node (ref "LED19") (pin "2") (pinfunction "2_2") (pintype "passive"))
      (node (ref "LED20") (pin "2") (pinfunction "2_2") (pintype "passive"))
      (node (ref "LED22") (pin "2") (pinfunction "2_2") (pintype "passive"))
      (node (ref "LED23") (pin "2") (pinfunction "2_2") (pintype "passive"))
      (node (ref "LED24") (pin "2") (pinfunction "2_2") (pintype "passive"))
      (node (ref "U4") (pin "14") (pinfunction "14_14") (pintype "passive"))
    )
    (net (code "21") (name "/GRID4") (class "Default")
      (node (ref "LED1") (pin "2") (pinfunction "2_2") (pintype "passive"))
      (node (ref "LED2") (pin "2") (pinfunction "2_2") (pintype "passive"))
      (node (ref "LED5") (pin "2") (pinfunction "2_2") (pintype "passive"))
      (node (ref "LED6") (pin "2") (pinfunction "2_2") (pintype "passive"))
      (node (ref "U4") (pin "12") (pinfunction "12_12") (pintype "passive"))
    )
    (net (code "22") (name "/GRID5") (class "Default")
      (node (ref "LED10") (pin "2") (pinfunction "2_2") (pintype "passive"))
      (node (ref "LED11") (pin "2") (pinfunction "2_2") (pintype "passive"))
      (node (ref "LED12") (pin "2") (pinfunction "2_2") (pintype "passive"))
      (node (ref "LED13") (pin "2") (pinfunction "2_2") (pintype "passive"))
      (node (ref "LED15") (pin "2") (pinfunction "2_2") (pintype "passive"))
      (node (ref "LED16") (pin "2") (pinfunction "2_2") (pintype "passive"))
      (node (ref "LED17") (pin "2") (pinfunction "2_2") (pintype "passive"))
      (node (ref "U4") (pin "11") (pinfunction "11_11") (pintype "passive"))
    )
    (net (code "23") (name "/IR") (class "Default")
      (node (ref "R25") (pin "1") (pinfunction "1_1") (pintype "passive"))
      (node (ref "U12") (pin "34") (pinfunction "34_34") (pintype "passive"))
    )
    (net (code "24") (name "/ISP_CK") (class "Default")
      (node (ref "J10") (pin "4") (pinfunction "4_4") (pintype "passive"))
      (node (ref "U12") (pin "44") (pinfunction "44_44") (pintype "passive"))
    )
    (net (code "25") (name "/ISP_DA") (class "Default")
      (node (ref "J10") (pin "3") (pinfunction "3_3") (pintype "passive"))
      (node (ref "U12") (pin "43") (pinfunction "43_43") (pintype "passive"))
    )
    (net (code "26") (name "/K1") (class "Default")
      (node (ref "K1") (pin "2") (pinfunction "2_2") (pintype "passive"))
      (node (ref "U12") (pin "26") (pinfunction "26_26") (pintype "passive"))
    )
    (net (code "27") (name "/K2") (class "Default")
      (node (ref "K2") (pin "2") (pinfunction "2_2") (pintype "passive"))
      (node (ref "U12") (pin "25") (pinfunction "25_25") (pintype "passive"))
    )
    (net (code "28") (name "/K5") (class "Default")
      (node (ref "K5") (pin "2") (pinfunction "2_2") (pintype "passive"))
      (node (ref "U12") (pin "20") (pinfunction "20_20") (pintype "passive"))
    )
    (net (code "29") (name "/K6") (class "Default")
      (node (ref "K6") (pin "2") (pinfunction "2_2") (pintype "passive"))
      (node (ref "U12") (pin "21") (pinfunction "21_21") (pintype "passive"))
    )
    (net (code "30") (name "/K9") (class "Default")
      (node (ref "K9") (pin "2") (pinfunction "2_2") (pintype "passive"))
      (node (ref "U12") (pin "28") (pinfunction "28_28") (pintype "passive"))
    )
    (net (code "31") (name "/K10") (class "Default")
      (node (ref "K10") (pin "2") (pinfunction "2_2") (pintype "passive"))
      (node (ref "U12") (pin "29") (pinfunction "29_29") (pintype "passive"))
    )
    (net (code "32") (name "/K11") (class "Default")
      (node (ref "K11") (pin "2") (pinfunction "2_2") (pintype "passive"))
      (node (ref "U12") (pin "30") (pinfunction "30_30") (pintype "passive"))
    )
    (net (code "33") (name "/K12") (class "Default")
      (node (ref "K12") (pin "2") (pinfunction "2_2") (pintype "passive"))
      (node (ref "U12") (pin "31") (pinfunction "31_31") (pintype "passive"))
    )
    (net (code "34") (name "/K14") (class "Default")
      (node (ref "K14") (pin "2") (pinfunction "2_2") (pintype "passive"))
      (node (ref "U12") (pin "19") (pinfunction "19_19") (pintype "passive"))
    )
    (net (code "35") (name "/K15") (class "Default")
      (node (ref "K15") (pin "2") (pinfunction "2_2") (pintype "passive"))
      (node (ref "U12") (pin "18") (pinfunction "18_18") (pintype "passive"))
    )
    (net (code "36") (name "/K16") (class "Default")
      (node (ref "K16") (pin "2") (pinfunction "2_2") (pintype "passive"))
      (node (ref "U12") (pin "17") (pinfunction "17_17") (pintype "passive"))
    )
    (net (code "37") (name "/K18") (class "Default")
      (node (ref "K18") (pin "2") (pinfunction "2_2") (pintype "passive"))
      (node (ref "U12") (pin "15") (pinfunction "15_15") (pintype "passive"))
    )
    (net (code "38") (name "/K19") (class "Default")
      (node (ref "K19") (pin "2") (pinfunction "2_2") (pintype "passive"))
      (node (ref "U12") (pin "14") (pinfunction "14_14") (pintype "passive"))
    )
    (net (code "39") (name "/L") (class "Default")
      (node (ref "J1") (pin "1") (pinfunction "1_1") (pintype "passive"))
      (node (ref "J2") (pin "2") (pinfunction "2_2") (pintype "passive"))
      (node (ref "R13") (pin "2") (pintype "passive"))
      (node (ref "R3") (pin "2") (pintype "passive"))
      (node (ref "R4") (pin "2") (pintype "passive"))
      (node (ref "R66") (pin "1") (pintype "passive"))
      (node (ref "R67") (pin "1") (pintype "passive"))
      (node (ref "TC1") (pin "2") (pintype "passive"))
      (node (ref "TR1") (pin "2") (pintype "passive"))
      (node (ref "TR2") (pin "2") (pintype "passive"))
      (node (ref "VDR1") (pin "1") (pinfunction "1_1") (pintype "passive"))
    )
    (net (code "40") (name "/LEG") (class "Default")
      (node (ref "C16") (pin "2") (pinfunction "2_2") (pintype "passive"))
      (node (ref "D1") (pin "1") (pinfunction "A_1") (pintype "passive"))
      (node (ref "J7") (pin "2") (pinfunction "2_2") (pintype "passive"))
      (node (ref "Q3") (pin "C") (pinfunction "C_C") (pintype "passive"))
    )
    (net (code "41") (name "/Left") (class "Default")
      (node (ref "C19") (pin "2") (pinfunction "2_2") (pintype "passive"))
      (node (ref "D5") (pin "1") (pinfunction "A_1") (pintype "passive"))
      (node (ref "J7") (pin "6") (pinfunction "6_6") (pintype "passive"))
      (node (ref "Q7") (pin "C") (pinfunction "C_C") (pintype "passive"))
    )
    (net (code "42") (name "/N") (class "Default")
      (node (ref "J1") (pin "2") (pinfunction "2_2") (pintype "passive"))
      (node (ref "J2") (pin "1") (pinfunction "1_1") (pintype "passive"))
      (node (ref "J3") (pin "2") (pinfunction "2_2") (pintype "passive"))
      (node (ref "J4") (pin "2") (pinfunction "2_2") (pintype "passive"))
      (node (ref "R1") (pin "2") (pintype "passive"))
      (node (ref "TC1") (pin "1") (pintype "passive"))
      (node (ref "VDR1") (pin "2") (pinfunction "2_2") (pintype "passive"))
    )
    (net (code "43") (name "/P_KEY") (class "Default")
      (node (ref "SW1") (pin "2") (pinfunction "2_2") (pintype "passive"))
      (node (ref "U12") (pin "5") (pinfunction "5_5") (pintype "passive"))
    )
    (net (code "44") (name "/Right") (class "Default")
      (node (ref "C21") (pin "2") (pinfunction "2_2") (pintype "passive"))
      (node (ref "D6") (pin "1") (pinfunction "A_1") (pintype "passive"))
      (node (ref "J7") (pin "8") (pinfunction "8_8") (pintype "passive"))
      (node (ref "Q9") (pin "C") (pinfunction "C_C") (pintype "passive"))
    )
    (net (code "45") (name "/S1_AD") (class "Default")
      (node (ref "R65") (pin "1") (pinfunction "1_1") (pintype "passive"))
      (node (ref "U12") (pin "36") (pinfunction "36_36") (pintype "passive"))
    )
    (net (code "46") (name "/S2_AD") (class "Default")
      (node (ref "R45") (pin "1") (pinfunction "1_1") (pintype "passive"))
      (node (ref "U12") (pin "35") (pinfunction "35_35") (pintype "passive"))
    )
    (net (code "47") (name "/SEGA") (class "Default")
      (node (ref "LED1") (pin "1") (pinfunction "1_1") (pintype "passive"))
      (node (ref "LED10") (pin "1") (pinfunction "1_1") (pintype "passive"))
      (node (ref "LED9") (pin "10") (pinfunction "a_10") (pintype "passive"))
      (node (ref "U4") (pin "2") (pinfunction "2_2") (pintype "passive"))
    )
    (net (code "48") (name "/SEGB") (class "Default")
      (node (ref "LED11") (pin "1") (pinfunction "1_1") (pintype "passive"))
      (node (ref "LED19") (pin "1") (pinfunction "1_1") (pintype "passive"))
      (node (ref "LED2") (pin "1") (pinfunction "1_1") (pintype "passive"))
      (node (ref "LED9") (pin "9") (pinfunction "b_9") (pintype "passive"))
      (node (ref "U4") (pin "3") (pinfunction "3_3") (pintype "passive"))
    )
    (net (code "49") (name "/SEGC") (class "Default")
      (node (ref "LED12") (pin "1") (pinfunction "1_1") (pintype "passive"))
      (node (ref "LED20") (pin "1") (pinfunction "1_1") (pintype "passive"))
      (node (ref "LED9") (pin "8") (pinfunction "c_8") (pintype "passive"))
      (node (ref "U4") (pin "4") (pinfunction "4_4") (pintype "passive"))
    )
    (net (code "50") (name "/SEGD") (class "Default")
      (node (ref "LED13") (pin "1") (pinfunction "1_1") (pintype "passive"))
      (node (ref "LED9") (pin "5") (pinfunction "d_5") (pintype "passive"))
      (node (ref "U4") (pin "5") (pinfunction "5_5") (pintype "passive"))
    )
    (net (code "51") (name "/SEGE") (class "Default")
      (node (ref "LED17") (pin "1") (pinfunction "1_1") (pintype "passive"))
      (node (ref "LED22") (pin "1") (pinfunction "1_1") (pintype "passive"))
      (node (ref "LED24") (pin "1") (pinfunction "1_1") (pintype "passive"))
      (node (ref "LED5") (pin "1") (pinfunction "1_1") (pintype "passive"))
      (node (ref "LED9") (pin "4") (pinfunction "e_4") (pintype "passive"))
      (node (ref "U4") (pin "6") (pinfunction "6_6") (pintype "passive"))
    )
    (net (code "52") (name "/SEGF") (class "Default")
      (node (ref "LED15") (pin "1") (pinfunction "1_1") (pintype "passive"))
      (node (ref "LED23") (pin "1") (pinfunction "1_1") (pintype "passive"))
      (node (ref "LED6") (pin "1") (pinfunction "1_1") (pintype "passive"))
      (node (ref "LED9") (pin "2") (pinfunction "f_2") (pintype "passive"))
      (node (ref "U4") (pin "7") (pinfunction "7_7") (pintype "passive"))
    )
    (net (code "53") (name "/SEGG") (class "Default")
      (node (ref "LED16") (pin "1") (pinfunction "1_1") (pintype "passive"))
      (node (ref "LED9") (pin "3") (pinfunction "g_3") (pintype "passive"))
      (node (ref "U4") (pin "8") (pinfunction "8_8") (pintype "passive"))
    )
    (net (code "54") (name "/Zero") (class "Default")
      (node (ref "R2") (pin "2") (pintype "passive"))
      (node (ref "U1") (pin "4") (pinfunction "COL_4") (pintype "passive"))
      (node (ref "U12") (pin "33") (pinfunction "33_33") (pintype "passive"))
    )
    (net (code "55") (name "5V") (class "Default")
      (node (ref "C1") (pin "2") (pinfunction "2_2") (pintype "passive"))
      (node (ref "C10") (pin "1") (pinfunction "1_1") (pintype "passive"))
      (node (ref "C2") (pin "2") (pinfunction "2_2") (pintype "passive"))
      (node (ref "C23") (pin "1") (pinfunction "1_1") (pintype "passive"))
      (node (ref "C8") (pin "1") (pinfunction "1_1") (pintype "passive"))
      (node (ref "C9") (pin "1") (pinfunction "1_1") (pintype "passive"))
      (node (ref "EC1") (pin "1") (pinfunction "1_1") (pintype "passive"))
      (node (ref "J10") (pin "1") (pinfunction "1_1") (pintype "passive"))
      (node (ref "L1") (pin "2") (pinfunction "2_2") (pintype "passive"))
      (node (ref "R14") (pin "1") (pintype "passive"))
      (node (ref "R2") (pin "1") (pintype "passive"))
      (node (ref "R20") (pin "1") (pinfunction "1_1") (pintype "passive"))
      (node (ref "R23") (pin "1") (pinfunction "1_1") (pintype "passive"))
      (node (ref "R28") (pin "1") (pinfunction "1_1") (pintype "passive"))
      (node (ref "R30") (pin "1") (pinfunction "1_1") (pintype "passive"))
      (node (ref "R48") (pin "1") (pinfunction "1_1") (pintype "passive"))
      (node (ref "R51") (pin "1") (pinfunction "1_1") (pintype "passive"))
      (node (ref "R6") (pin "1") (pintype "passive"))
      (node (ref "U10") (pin "4") (pinfunction "4_4") (pintype "passive"))
      (node (ref "U12") (pin "37") (pinfunction "37_37") (pintype "passive"))
      (node (ref "U13") (pin "4") (pinfunction "4_4") (pintype "passive"))
      (node (ref "U4") (pin "1") (pinfunction "1_1") (pintype "passive"))
      (node (ref "U7") (pin "6") (pinfunction "6_6") (pintype "passive"))
    )
    (net (code "56") (name "GND") (class "Default")
      (node (ref "BUZZ1") (pin "1") (pinfunction "1_1") (pintype "passive"))
      (node (ref "C1") (pin "1") (pinfunction "1_1") (pintype "passive"))
      (node (ref "C10") (pin "2") (pinfunction "2_2") (pintype "passive"))
      (node (ref "C12") (pin "1") (pinfunction "1_1") (pintype "passive"))
      (node (ref "C13") (pin "1") (pinfunction "1_1") (pintype "passive"))
      (node (ref "C14") (pin "2") (pinfunction "2_2") (pintype "passive"))
      (node (ref "C15") (pin "1") (pinfunction "1_1") (pintype "passive"))
      (node (ref "C17") (pin "1") (pinfunction "1_1") (pintype "passive"))
      (node (ref "C2") (pin "1") (pinfunction "1_1") (pintype "passive"))
      (node (ref "C23") (pin "2") (pinfunction "2_2") (pintype "passive"))
      (node (ref "C25") (pin "1") (pinfunction "1_1") (pintype "passive"))
      (node (ref "C3") (pin "2") (pinfunction "2_2") (pintype "passive"))
      (node (ref "C4") (pin "2") (pinfunction "2_2") (pintype "passive"))
      (node (ref "C6") (pin "2") (pinfunction "2_2") (pintype "passive"))
      (node (ref "C7") (pin "1") (pinfunction "1_1") (pintype "passive"))
      (node (ref "C8") (pin "2") (pinfunction "2_2") (pintype "passive"))
      (node (ref "C9") (pin "2") (pinfunction "2_2") (pintype "passive"))
      (node (ref "EC1") (pin "2") (pinfunction "2_2") (pintype "passive"))
      (node (ref "J10") (pin "2") (pinfunction "2_2") (pintype "passive"))
      (node (ref "J5") (pin "2") (pinfunction "2_2") (pintype "passive"))
      (node (ref "L2") (pin "1") (pinfunction "1_1") (pintype "passive"))
      (node (ref "L3") (pin "1") (pinfunction "1_1") (pintype "passive"))
      (node (ref "Q1") (pin "E") (pinfunction "E_E") (pintype "passive"))
      (node (ref "Q2") (pin "E") (pinfunction "E_E") (pintype "passive"))
      (node (ref "Q3") (pin "E") (pinfunction "E_E") (pintype "passive"))
      (node (ref "Q4") (pin "E") (pinfunction "E_E") (pintype "passive"))
      (node (ref "Q5") (pin "E") (pinfunction "E_E") (pintype "passive"))
      (node (ref "Q6") (pin "E") (pinfunction "E_E") (pintype "passive"))
      (node (ref "Q7") (pin "E") (pinfunction "E_E") (pintype "passive"))
      (node (ref "Q8") (pin "E") (pinfunction "E_E") (pintype "passive"))
      (node (ref "Q9") (pin "E") (pinfunction "E_E") (pintype "passive"))
      (node (ref "R15") (pin "2") (pintype "passive"))
      (node (ref "R17") (pin "2") (pinfunction "2_2") (pintype "passive"))
      (node (ref "R21") (pin "2") (pinfunction "2_2") (pintype "passive"))
      (node (ref "R27") (pin "2") (pintype "passive"))
      (node (ref "R29") (pin "2") (pinfunction "2_2") (pintype "passive"))
      (node (ref "R32") (pin "2") (pintype "passive"))
      (node (ref "R36") (pin "2") (pinfunction "2_2") (pintype "passive"))
      (node (ref "R38") (pin "2") (pinfunction "2_2") (pintype "passive"))
      (node (ref "R40") (pin "2") (pintype "passive"))
      (node (ref "R42") (pin "2") (pintype "passive"))
      (node (ref "R49") (pin "2") (pinfunction "2_2") (pintype "passive"))
      (node (ref "R50") (pin "2") (pintype "passive"))
      (node (ref "R55") (pin "2") (pintype "passive"))
      (node (ref "R56") (pin "2") (pinfunction "2_2") (pintype "passive"))
      (node (ref "R58") (pin "2") (pinfunction "2_2") (pintype "passive"))
      (node (ref "R61") (pin "2") (pintype "passive"))
      (node (ref "R7") (pin "2") (pintype "passive"))
      (node (ref "SW1") (pin "1") (pinfunction "1_1") (pintype "passive"))
      (node (ref "U1") (pin "3") (pinfunction "EM_3") (pintype "passive"))
      (node (ref "U10") (pin "11") (pinfunction "11_11") (pintype "passive"))
      (node (ref "U12") (pin "40") (pinfunction "40_40") (pintype "passive"))
      (node (ref "U13") (pin "11") (pinfunction "11_11") (pintype "passive"))
      (node (ref "U4") (pin "10") (pinfunction "10_10") (pintype "passive"))
      (node (ref "U6") (pin "2") (pinfunction "2_2") (pintype "passive"))
      (node (ref "U7") (pin "8") (pinfunction "8_8") (pintype "passive"))
      (node (ref "U9") (pin "1") (pinfunction "1_1") (pintype "passive"))
      (node (ref "U9") (pin "6") (pinfunction "6_6") (pintype "passive"))
      (node (ref "Y1") (pin "2") (pinfunction "OSC2_2") (pintype "passive"))
    )
    (net (code "57") (name "Net-(BUZZ1-Pad2)") (class "Default")
      (node (ref "BUZZ1") (pin "2") (pinfunction "2_2") (pintype "passive"))
      (node (ref "R18") (pin "1") (pinfunction "1_1") (pintype "passive"))
      (node (ref "R21") (pin "1") (pinfunction "1_1") (pintype "passive"))
    )
    (net (code "58") (name "Net-(C5-Pad1)") (class "Default")
      (node (ref "C5") (pin "1") (pinfunction "1_1") (pintype "passive"))
      (node (ref "U6") (pin "1") (pinfunction "1_1") (pintype "passive"))
    )
    (net (code "59") (name "Net-(C5-Pad2)") (class "Default")
      (node (ref "C5") (pin "2") (pinfunction "2_2") (pintype "passive"))
      (node (ref "L1") (pin "1") (pinfunction "1_1") (pintype "passive"))
      (node (ref "R24") (pin "2") (pinfunction "2_2") (pintype "passive"))
      (node (ref "U6") (pin "6") (pinfunction "6_6") (pintype "passive"))
    )
    (net (code "60") (name "Net-(C6-Pad1)") (class "Default")
      (node (ref "C6") (pin "1") (pinfunction "1_1") (pintype "passive"))
      (node (ref "R23") (pin "2") (pinfunction "2_2") (pintype "passive"))
      (node (ref "U9") (pin "3") (pinfunction "3_3") (pintype "passive"))
    )
    (net (code "61") (name "Net-(C7-Pad2)") (class "Default")
      (node (ref "C7") (pin "2") (pinfunction "2_2") (pintype "passive"))
      (node (ref "R24") (pin "1") (pinfunction "1_1") (pintype "passive"))
    )
    (net (code "62") (name "Net-(C11-Pad2)") (class "Default")
      (node (ref "C11") (pin "2") (pinfunction "2_2") (pintype "passive"))
      (node (ref "L2") (pin "2") (pinfunction "2_2") (pintype "passive"))
      (node (ref "U9") (pin "2") (pinfunction "2_2") (pintype "passive"))
    )
    (net (code "63") (name "Net-(C12-Pad2)") (class "Default")
      (node (ref "C12") (pin "2") (pinfunction "2_2") (pintype "passive"))
      (node (ref "U10") (pin "1") (pinfunction "1_1") (pintype "passive"))
      (node (ref "U8") (pin "2") (pinfunction "2_2") (pintype "passive"))
    )
    (net (code "64") (name "Net-(C14-Pad1)") (class "Default")
      (node (ref "C14") (pin "1") (pinfunction "1_1") (pintype "passive"))
      (node (ref "U9") (pin "4") (pinfunction "4_4") (pintype "passive"))
    )
    (net (code "65") (name "Net-(C15-Pad2)") (class "Default")
      (node (ref "C15") (pin "2") (pinfunction "2_2") (pintype "passive"))
      (node (ref "R30") (pin "2") (pinfunction "2_2") (pintype "passive"))
      (node (ref "R34") (pin "2") (pinfunction "2_2") (pintype "passive"))
      (node (ref "R38") (pin "1") (pinfunction "1_1") (pintype "passive"))
    )
    (net (code "66") (name "Net-(C17-Pad2)") (class "Default")
      (node (ref "C17") (pin "2") (pinfunction "2_2") (pintype "passive"))
      (node (ref "U11") (pin "2") (pinfunction "2_2") (pintype "passive"))
      (node (ref "U13") (pin "1") (pinfunction "1_1") (pintype "passive"))
    )
    (net (code "67") (name "Net-(C25-Pad2)") (class "Default")
      (node (ref "C25") (pin "2") (pinfunction "2_2") (pintype "passive"))
      (node (ref "R51") (pin "2") (pinfunction "2_2") (pintype "passive"))
      (node (ref "R54") (pin "2") (pinfunction "2_2") (pintype "passive"))
      (node (ref "R58") (pin "1") (pinfunction "1_1") (pintype "passive"))
    )
    (net (code "68") (name "Net-(C26-Pad1)") (class "Default")
      (node (ref "C26") (pin "1") (pinfunction "1_1") (pintype "passive"))
      (node (ref "R66") (pin "2") (pintype "passive"))
    )
    (net (code "69") (name "Net-(C26-Pad2)") (class "Default")
      (node (ref "C26") (pin "2") (pinfunction "2_2") (pintype "passive"))
      (node (ref "J3") (pin "1") (pinfunction "1_1") (pintype "passive"))
      (node (ref "TR1") (pin "1") (pintype "passive"))
    )
    (net (code "70") (name "Net-(C27-Pad1)") (class "Default")
      (node (ref "C27") (pin "1") (pinfunction "1_1") (pintype "passive"))
      (node (ref "R67") (pin "2") (pintype "passive"))
    )
    (net (code "71") (name "Net-(C27-Pad2)") (class "Default")
      (node (ref "C27") (pin "2") (pinfunction "2_2") (pintype "passive"))
      (node (ref "J4") (pin "1") (pinfunction "1_1") (pintype "passive"))
      (node (ref "TR2") (pin "1") (pintype "passive"))
    )
    (net (code "72") (name "Net-(D7-A)") (class "Default")
      (node (ref "C20") (pin "2") (pinfunction "2_2") (pintype "passive"))
      (node (ref "D7") (pin "1") (pinfunction "A_1") (pintype "passive"))
      (node (ref "J9") (pin "1") (pinfunction "1_1") (pintype "passive"))
      (node (ref "Q8") (pin "C") (pinfunction "C_C") (pintype "passive"))
    )
    (net (code "73") (name "Net-(J6-Pad1)") (class "Default")
      (node (ref "J6") (pin "1") (pinfunction "1_1") (pintype "passive"))
      (node (ref "U7") (pin "5") (pinfunction "5_5") (pintype "passive"))
    )
    (net (code "74") (name "Net-(J6-Pad2)") (class "Default")
      (node (ref "J6") (pin "2") (pinfunction "2_2") (pintype "passive"))
      (node (ref "U7") (pin "7") (pinfunction "7_7") (pintype "passive"))
    )
    (net (code "75") (name "Net-(Q1-PadB)") (class "Default")
      (node (ref "Q1") (pin "B") (pinfunction "B_B") (pintype "passive"))
      (node (ref "R7") (pin "1") (pintype "passive"))
      (node (ref "R9") (pin "2") (pintype "passive"))
    )
    (net (code "76") (name "Net-(Q2-PadB)") (class "Default")
      (node (ref "Q2") (pin "B") (pinfunction "B_B") (pintype "passive"))
      (node (ref "R15") (pin "1") (pintype "passive"))
      (node (ref "R16") (pin "2") (pintype "passive"))
    )
    (net (code "77") (name "Net-(Q3-PadB)") (class "Default")
      (node (ref "Q3") (pin "B") (pinfunction "B_B") (pintype "passive"))
      (node (ref "R27") (pin "1") (pintype "passive"))
      (node (ref "R33") (pin "1") (pintype "passive"))
    )
    (net (code "78") (name "Net-(Q4-PadB)") (class "Default")
      (node (ref "Q4") (pin "B") (pinfunction "B_B") (pintype "passive"))
      (node (ref "R32") (pin "1") (pintype "passive"))
      (node (ref "R35") (pin "1") (pintype "passive"))
    )
    (net (code "79") (name "Net-(Q5-PadB)") (class "Default")
      (node (ref "Q5") (pin "B") (pinfunction "B_B") (pintype "passive"))
      (node (ref "R40") (pin "1") (pintype "passive"))
      (node (ref "R44") (pin "2") (pintype "passive"))
    )
    (net (code "80") (name "Net-(Q6-PadB)") (class "Default")
      (node (ref "Q6") (pin "B") (pinfunction "B_B") (pintype "passive"))
      (node (ref "R42") (pin "1") (pintype "passive"))
      (node (ref "R46") (pin "1") (pintype "passive"))
    )
    (net (code "81") (name "Net-(Q7-PadB)") (class "Default")
      (node (ref "Q7") (pin "B") (pinfunction "B_B") (pintype "passive"))
      (node (ref "R50") (pin "1") (pintype "passive"))
      (node (ref "R53") (pin "2") (pintype "passive"))
    )
    (net (code "82") (name "Net-(Q8-PadB)") (class "Default")
      (node (ref "Q8") (pin "B") (pinfunction "B_B") (pintype "passive"))
      (node (ref "R55") (pin "1") (pintype "passive"))
      (node (ref "R60") (pin "1") (pintype "passive"))
    )
    (net (code "83") (name "Net-(Q9-PadB)") (class "Default")
      (node (ref "Q9") (pin "B") (pinfunction "B_B") (pintype "passive"))
      (node (ref "R61") (pin "1") (pintype "passive"))
      (node (ref "R64") (pin "2") (pintype "passive"))
    )
    (net (code "84") (name "Net-(R1-Pad1)") (class "Default")
      (node (ref "R1") (pin "1") (pintype "passive"))
      (node (ref "U2") (pin "AC2") (pinfunction "～_AC2") (pintype "passive"))
    )
    (net (code "85") (name "Net-(R3-Pad1)") (class "Default")
      (node (ref "R3") (pin "1") (pintype "passive"))
      (node (ref "U2") (pin "AC1") (pinfunction "～_AC1") (pintype "passive"))
    )
    (net (code "86") (name "Net-(R4-Pad1)") (class "Default")
      (node (ref "R4") (pin "1") (pintype "passive"))
      (node (ref "R5") (pin "1") (pintype "passive"))
    )
    (net (code "87") (name "Net-(R8-Pad2)") (class "Default")
      (node (ref "R8") (pin "2") (pinfunction "2_2") (pintype "passive"))
      (node (ref "U4") (pin "16") (pinfunction "16_16") (pintype "passive"))
    )
    (net (code "88") (name "Net-(R12-Pad1)") (class "Default")
      (node (ref "R12") (pin "1") (pintype "passive"))
      (node (ref "R13") (pin "1") (pintype "passive"))
    )
    (net (code "89") (name "Net-(R17-Pad1)") (class "Default")
      (node (ref "R17") (pin "1") (pinfunction "1_1") (pintype "passive"))
      (node (ref "R20") (pin "2") (pinfunction "2_2") (pintype "passive"))
      (node (ref "U6") (pin "3") (pinfunction "3_3") (pintype "passive"))
    )
    (net (code "90") (name "Net-(R19-Pad2)") (class "Default")
      (node (ref "R19") (pin "2") (pinfunction "2_2") (pintype "passive"))
      (node (ref "U6") (pin "4") (pinfunction "4_4") (pintype "passive"))
    )
    (net (code "91") (name "Net-(R22-Pad2)") (class "Default")
      (node (ref "R22") (pin "2") (pinfunction "2_2") (pintype "passive"))
      (node (ref "U7") (pin "2") (pinfunction "2_2") (pintype "passive"))
    )
    (net (code "92") (name "Net-(R25-Pad2)") (class "Default")
      (node (ref "R25") (pin "2") (pinfunction "2_2") (pintype "passive"))
      (node (ref "U9") (pin "5") (pinfunction "5_5") (pintype "passive"))
    )
    (net (code "93") (name "Net-(R26-Pad1)") (class "Default")
      (node (ref "R26") (pin "1") (pinfunction "1_1") (pintype "passive"))
      (node (ref "R31") (pin "1") (pinfunction "1_1") (pintype "passive"))
      (node (ref "U10") (pin "14") (pinfunction "14_14") (pintype "passive"))
    )
    (net (code "94") (name "Net-(R26-Pad2)") (class "Default")
      (node (ref "R26") (pin "2") (pinfunction "2_2") (pintype "passive"))
      (node (ref "R34") (pin "1") (pinfunction "1_1") (pintype "passive"))
      (node (ref "U10") (pin "5") (pinfunction "5_5") (pintype "passive"))
    )
    (net (code "95") (name "Net-(R28-Pad2)") (class "Default")
      (node (ref "R28") (pin "2") (pinfunction "2_2") (pintype "passive"))
      (node (ref "R36") (pin "1") (pinfunction "1_1") (pintype "passive"))
      (node (ref "U10") (pin "3") (pinfunction "3_3") (pintype "passive"))
    )
    (net (code "96") (name "Net-(R29-Pad1)") (class "Default")
      (node (ref "R29") (pin "1") (pinfunction "1_1") (pintype "passive"))
      (node (ref "U10") (pin "2") (pinfunction "2_2") (pintype "passive"))
      (node (ref "U8") (pin "5") (pinfunction "5_5") (pintype "passive"))
    )
    (net (code "97") (name "Net-(R31-Pad2)") (class "Default")
      (node (ref "R31") (pin "2") (pinfunction "2_2") (pintype "passive"))
      (node (ref "R37") (pin "1") (pinfunction "1_1") (pintype "passive"))
      (node (ref "U10") (pin "13") (pinfunction "13_13") (pintype "passive"))
    )
    (net (code "98") (name "Net-(R37-Pad2)") (class "Default")
      (node (ref "R37") (pin "2") (pinfunction "2_2") (pintype "passive"))
      (node (ref "R41") (pin "2") (pinfunction "2_2") (pintype "passive"))
      (node (ref "U10") (pin "9") (pinfunction "9_9") (pintype "passive"))
    )
    (net (code "99") (name "Net-(R39-Pad1)") (class "Default")
      (node (ref "R39") (pin "1") (pinfunction "1_1") (pintype "passive"))
      (node (ref "R43") (pin "2") (pinfunction "2_2") (pintype "passive"))
      (node (ref "U10") (pin "6") (pinfunction "6_6") (pintype "passive"))
    )
    (net (code "100") (name "Net-(R39-Pad2)") (class "Default")
      (node (ref "R39") (pin "2") (pinfunction "2_2") (pintype "passive"))
      (node (ref "R45") (pin "2") (pinfunction "2_2") (pintype "passive"))
      (node (ref "U10") (pin "7") (pinfunction "7_7") (pintype "passive"))
    )
    (net (code "101") (name "Net-(R41-Pad1)") (class "Default")
      (node (ref "R41") (pin "1") (pinfunction "1_1") (pintype "passive"))
      (node (ref "R43") (pin "1") (pinfunction "1_1") (pintype "passive"))
      (node (ref "U10") (pin "8") (pinfunction "8_8") (pintype "passive"))
    )
    (net (code "102") (name "Net-(R47-Pad1)") (class "Default")
      (node (ref "R47") (pin "1") (pinfunction "1_1") (pintype "passive"))
      (node (ref "R52") (pin "1") (pinfunction "1_1") (pintype "passive"))
      (node (ref "U13") (pin "14") (pinfunction "14_14") (pintype "passive"))
    )
    (net (code "103") (name "Net-(R47-Pad2)") (class "Default")
      (node (ref "R47") (pin "2") (pinfunction "2_2") (pintype "passive"))
      (node (ref "R54") (pin "1") (pinfunction "1_1") (pintype "passive"))
      (node (ref "U13") (pin "5") (pinfunction "5_5") (pintype "passive"))
    )
    (net (code "104") (name "Net-(R48-Pad2)") (class "Default")
      (node (ref "R48") (pin "2") (pinfunction "2_2") (pintype "passive"))
      (node (ref "R56") (pin "1") (pinfunction "1_1") (pintype "passive"))
      (node (ref "U13") (pin "3") (pinfunction "3_3") (pintype "passive"))
    )
    (net (code "105") (name "Net-(R49-Pad1)") (class "Default")
      (node (ref "R49") (pin "1") (pinfunction "1_1") (pintype "passive"))
      (node (ref "U11") (pin "5") (pinfunction "5_5") (pintype "passive"))
      (node (ref "U13") (pin "2") (pinfunction "2_2") (pintype "passive"))
    )
    (net (code "106") (name "Net-(R52-Pad2)") (class "Default")
      (node (ref "R52") (pin "2") (pinfunction "2_2") (pintype "passive"))
      (node (ref "R57") (pin "1") (pinfunction "1_1") (pintype "passive"))
      (node (ref "U13") (pin "13") (pinfunction "13_13") (pintype "passive"))
    )
    (net (code "107") (name "Net-(R57-Pad2)") (class "Default")
      (node (ref "R57") (pin "2") (pinfunction "2_2") (pintype "passive"))
      (node (ref "R62") (pin "2") (pinfunction "2_2") (pintype "passive"))
      (node (ref "U13") (pin "9") (pinfunction "9_9") (pintype "passive"))
    )
    (net (code "108") (name "Net-(R59-Pad1)") (class "Default")
      (node (ref "R59") (pin "1") (pinfunction "1_1") (pintype "passive"))
      (node (ref "R63") (pin "2") (pinfunction "2_2") (pintype "passive"))
      (node (ref "U13") (pin "6") (pinfunction "6_6") (pintype "passive"))
    )
    (net (code "109") (name "Net-(R59-Pad2)") (class "Default")
      (node (ref "R59") (pin "2") (pinfunction "2_2") (pintype "passive"))
      (node (ref "R65") (pin "2") (pinfunction "2_2") (pintype "passive"))
      (node (ref "U13") (pin "7") (pinfunction "7_7") (pintype "passive"))
    )
    (net (code "110") (name "Net-(R62-Pad1)") (class "Default")
      (node (ref "R62") (pin "1") (pinfunction "1_1") (pintype "passive"))
      (node (ref "R63") (pin "1") (pinfunction "1_1") (pintype "passive"))
      (node (ref "U13") (pin "8") (pinfunction "8_8") (pintype "passive"))
    )
    (net (code "111") (name "Net-(R68-Pad2)") (class "Default")
      (node (ref "R68") (pin "2") (pinfunction "2_2") (pintype "passive"))
      (node (ref "U7") (pin "1") (pinfunction "1_1") (pintype "passive"))
    )
    (net (code "112") (name "Net-(U1-AN)") (class "Default")
      (node (ref "U1") (pin "1") (pinfunction "AN_1") (pintype "passive"))
      (node (ref "U2") (pin "V+") (pinfunction "+_V+") (pintype "passive"))
    )
    (net (code "113") (name "Net-(U1-CAT)") (class "Default")
      (node (ref "U1") (pin "2") (pinfunction "CAT_2") (pintype "passive"))
      (node (ref "U2") (pin "V-") (pinfunction "-_V-") (pintype "passive"))
    )
    (net (code "114") (name "Net-(U3-A)") (class "Default")
      (node (ref "R6") (pin "2") (pintype "passive"))
      (node (ref "U3") (pin "1") (pinfunction "A_1") (pintype "passive"))
    )
    (net (code "115") (name "Net-(U3-C)") (class "Default")
      (node (ref "Q1") (pin "C") (pinfunction "C_C") (pintype "passive"))
      (node (ref "U3") (pin "2") (pinfunction "C_2") (pintype "passive"))
    )
    (net (code "116") (name "Net-(U3-MT1)") (class "Default")
      (node (ref "R5") (pin "2") (pintype "passive"))
      (node (ref "U3") (pin "6") (pinfunction "MT1_6") (pintype "passive"))
    )
    (net (code "117") (name "Net-(U3-MT2)") (class "Default")
      (node (ref "TR1") (pin "3") (pintype "passive"))
      (node (ref "U3") (pin "4") (pinfunction "MT2_4") (pintype "passive"))
    )
    (net (code "118") (name "Net-(U5-A)") (class "Default")
      (node (ref "R14") (pin "2") (pintype "passive"))
      (node (ref "U5") (pin "1") (pinfunction "A_1") (pintype "passive"))
    )
    (net (code "119") (name "Net-(U5-C)") (class "Default")
      (node (ref "Q2") (pin "C") (pinfunction "C_C") (pintype "passive"))
      (node (ref "U5") (pin "2") (pinfunction "C_2") (pintype "passive"))
    )
    (net (code "120") (name "Net-(U5-MT1)") (class "Default")
      (node (ref "R12") (pin "2") (pintype "passive"))
      (node (ref "U5") (pin "6") (pinfunction "MT1_6") (pintype "passive"))
    )
    (net (code "121") (name "Net-(U5-MT2)") (class "Default")
      (node (ref "TR2") (pin "3") (pintype "passive"))
      (node (ref "U5") (pin "4") (pinfunction "MT2_4") (pintype "passive"))
    )
    (net (code "122") (name "Net-(U10-Pad10)") (class "Default")
      (node (ref "U10") (pin "10") (pinfunction "10_10") (pintype "passive"))
      (node (ref "U8") (pin "1") (pinfunction "1_1") (pintype "passive"))
      (node (ref "U8") (pin "6") (pinfunction "6_6") (pintype "passive"))
    )
    (net (code "123") (name "Net-(U10-Pad12)") (class "Default")
      (node (ref "U10") (pin "12") (pinfunction "12_12") (pintype "passive"))
      (node (ref "U8") (pin "3") (pinfunction "3_3") (pintype "passive"))
    )
    (net (code "124") (name "Net-(U11-Pad1)") (class "Default")
      (node (ref "U11") (pin "1") (pinfunction "1_1") (pintype "passive"))
      (node (ref "U11") (pin "6") (pinfunction "6_6") (pintype "passive"))
      (node (ref "U13") (pin "10") (pinfunction "10_10") (pintype "passive"))
    )
    (net (code "125") (name "Net-(U11-Pad3)") (class "Default")
      (node (ref "U11") (pin "3") (pinfunction "3_3") (pintype "passive"))
      (node (ref "U13") (pin "12") (pinfunction "12_12") (pintype "passive"))
    )
    (net (code "126") (name "Net-(Y1-OSC1)") (class "Default")
      (node (ref "U9") (pin "8") (pinfunction "8_8") (pintype "passive"))
      (node (ref "Y1") (pin "1") (pinfunction "OSC1_1") (pintype "passive"))
    )
    (net (code "127") (name "unconnected-(LED9-Neg-x8-Pad6)") (class "Default")
      (node (ref "LED9") (pin "6") (pinfunction "Neg-x8_6") (pintype "passive"))
    )
    (net (code "128") (name "unconnected-(LED9-dp-Pad7)") (class "Default")
      (node (ref "LED9") (pin "7") (pinfunction "dp_7") (pintype "passive"))
    )
    (net (code "129") (name "unconnected-(U3-NC-Pad3)") (class "Default")
      (node (ref "U3") (pin "3") (pinfunction "NC_3") (pintype "passive+no_connect"))
    )
    (net (code "130") (name "unconnected-(U3-SBU-Pad5)") (class "Default")
      (node (ref "U3") (pin "5") (pinfunction "SBU_5") (pintype "passive+no_connect"))
    )
    (net (code "131") (name "unconnected-(U4-Pad9)") (class "Default")
      (node (ref "U4") (pin "9") (pinfunction "9_9") (pintype "passive"))
    )
    (net (code "132") (name "unconnected-(U4-Pad13)") (class "Default")
      (node (ref "U4") (pin "13") (pinfunction "13_13") (pintype "passive"))
    )
    (net (code "133") (name "unconnected-(U5-NC-Pad3)") (class "Default")
      (node (ref "U5") (pin "3") (pinfunction "NC_3") (pintype "passive+no_connect"))
    )
    (net (code "134") (name "unconnected-(U5-SBU-Pad5)") (class "Default")
      (node (ref "U5") (pin "5") (pinfunction "SBU_5") (pintype "passive+no_connect"))
    )
    (net (code "135") (name "unconnected-(U7-Pad3)") (class "Default")
      (node (ref "U7") (pin "3") (pinfunction "3_3") (pintype "passive"))
    )
    (net (code "136") (name "unconnected-(U7-Pad4)") (class "Default")
      (node (ref "U7") (pin "4") (pinfunction "4_4") (pintype "passive"))
    )
    (net (code "137") (name "unconnected-(U8-Pad4)") (class "Default")
      (node (ref "U8") (pin "4") (pinfunction "4_4") (pintype "passive+no_connect"))
    )
    (net (code "138") (name "unconnected-(U9-Pad7)") (class "Default")
      (node (ref "U9") (pin "7") (pinfunction "7_7") (pintype "passive+no_connect"))
    )
    (net (code "139") (name "unconnected-(U11-Pad4)") (class "Default")
      (node (ref "U11") (pin "4") (pinfunction "4_4") (pintype "passive+no_connect"))
    )
    (net (code "140") (name "unconnected-(U12-Pad1)") (class "Default")
      (node (ref "U12") (pin "1") (pinfunction "1_1") (pintype "passive"))
    )
    (net (code "141") (name "unconnected-(U12-Pad3)") (class "Default")
      (node (ref "U12") (pin "3") (pinfunction "3_3") (pintype "passive"))
    )
    (net (code "142") (name "unconnected-(U12-Pad13)") (class "Default")
      (node (ref "U12") (pin "13") (pinfunction "13_13") (pintype "passive"))
    )
    (net (code "143") (name "unconnected-(U12-Pad16)") (class "Default")
      (node (ref "U12") (pin "16") (pinfunction "16_16") (pintype "passive"))
    )
    (net (code "144") (name "unconnected-(U12-Pad22)") (class "Default")
      (node (ref "U12") (pin "22") (pinfunction "22_22") (pintype "passive"))
    )
    (net (code "145") (name "unconnected-(U12-Pad23)") (class "Default")
      (node (ref "U12") (pin "23") (pinfunction "23_23") (pintype "passive"))
    )
    (net (code "146") (name "unconnected-(U12-Pad24)") (class "Default")
      (node (ref "U12") (pin "24") (pinfunction "24_24") (pintype "passive"))
    )
    (net (code "147") (name "unconnected-(U12-Pad27)") (class "Default")
      (node (ref "U12") (pin "27") (pinfunction "27_27") (pintype "passive"))
    )
    (net (code "148") (name "unconnected-(U12-Pad32)") (class "Default")
      (node (ref "U12") (pin "32") (pinfunction "32_32") (pintype "passive"))
    )
  )
)
